# IMU_NoPilot.net
KiCad netlist of a schematic drawn in EAGLE
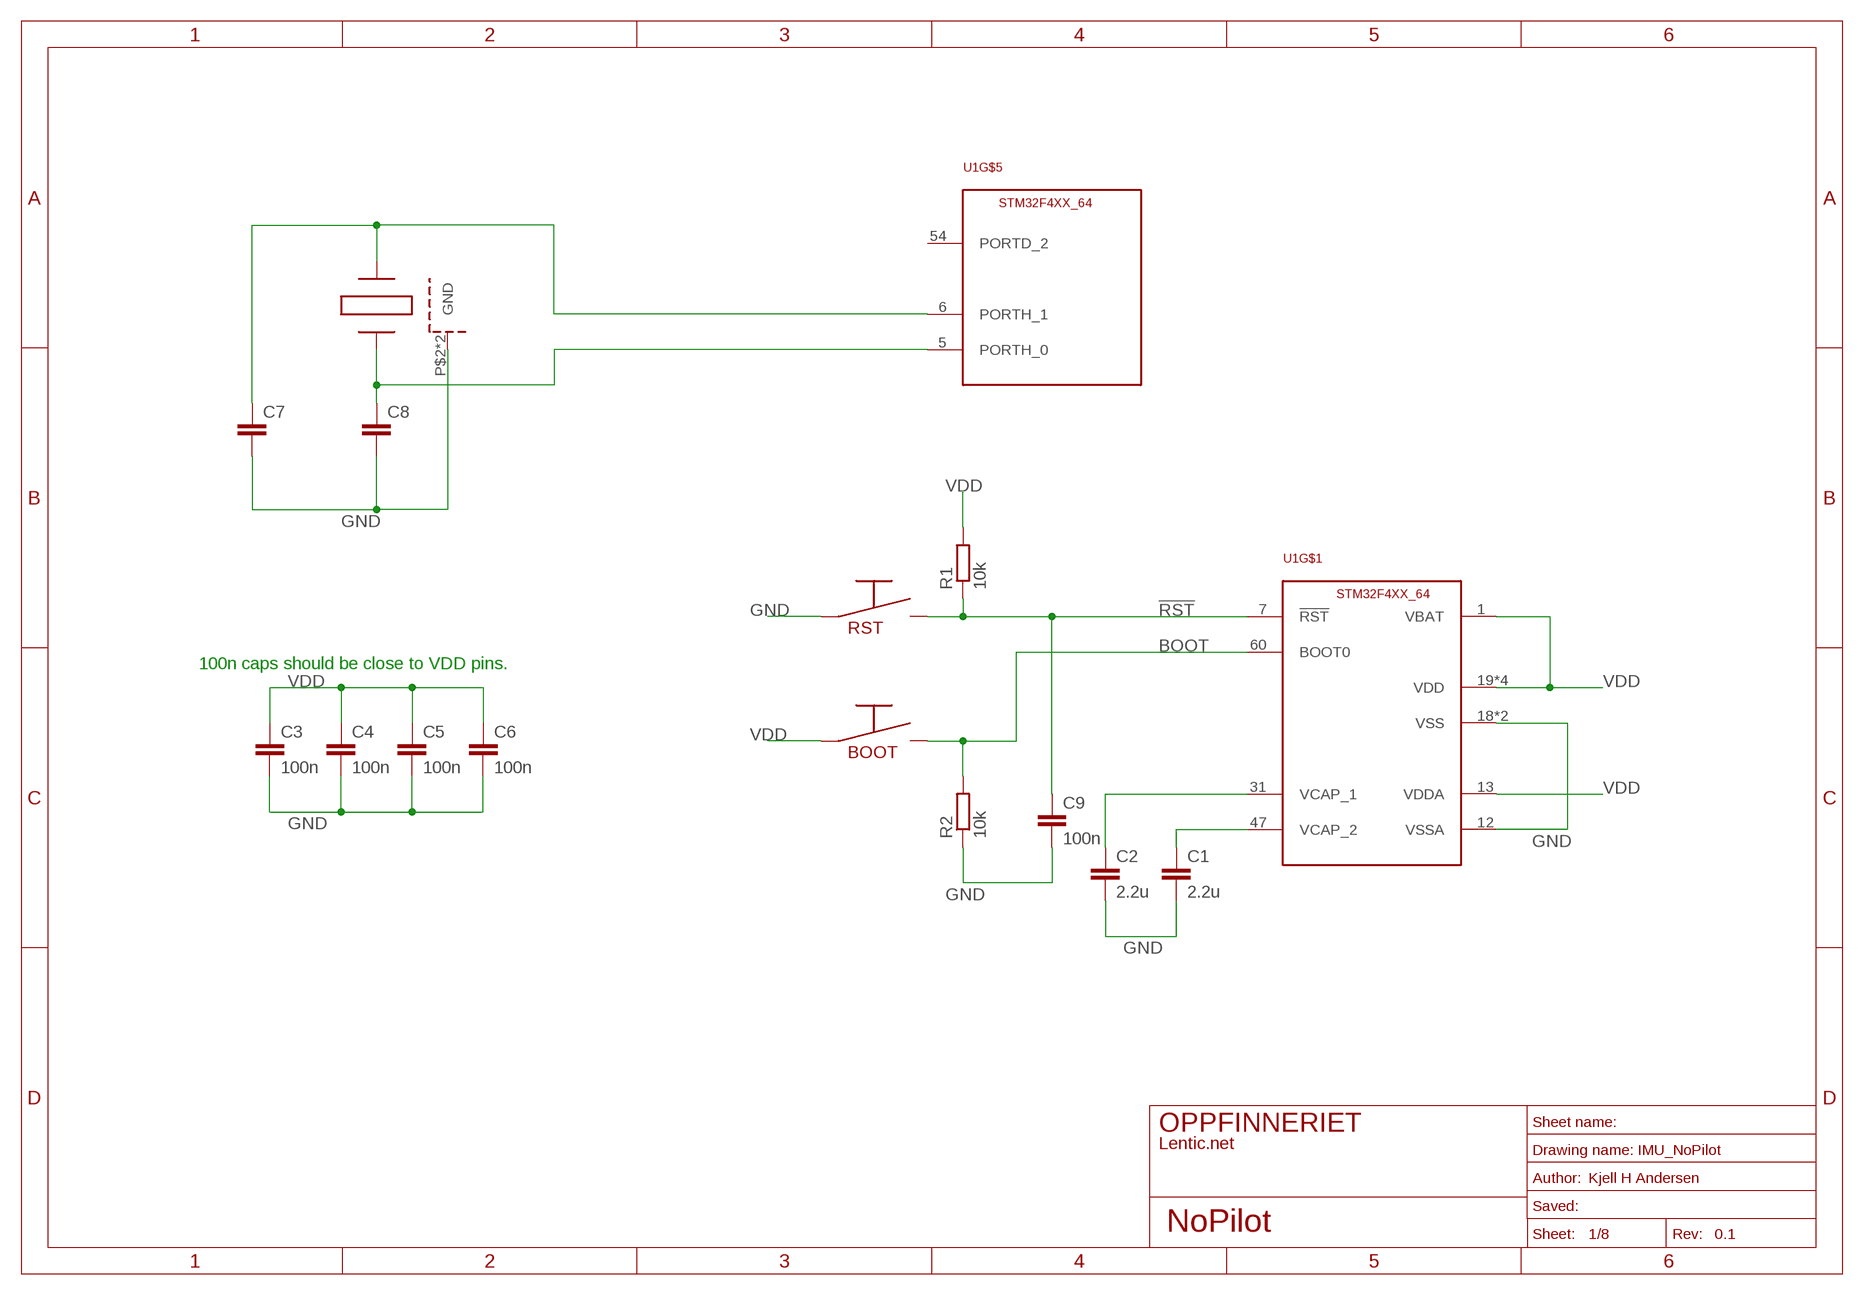
[diagram p0: schematic, sheet 1]
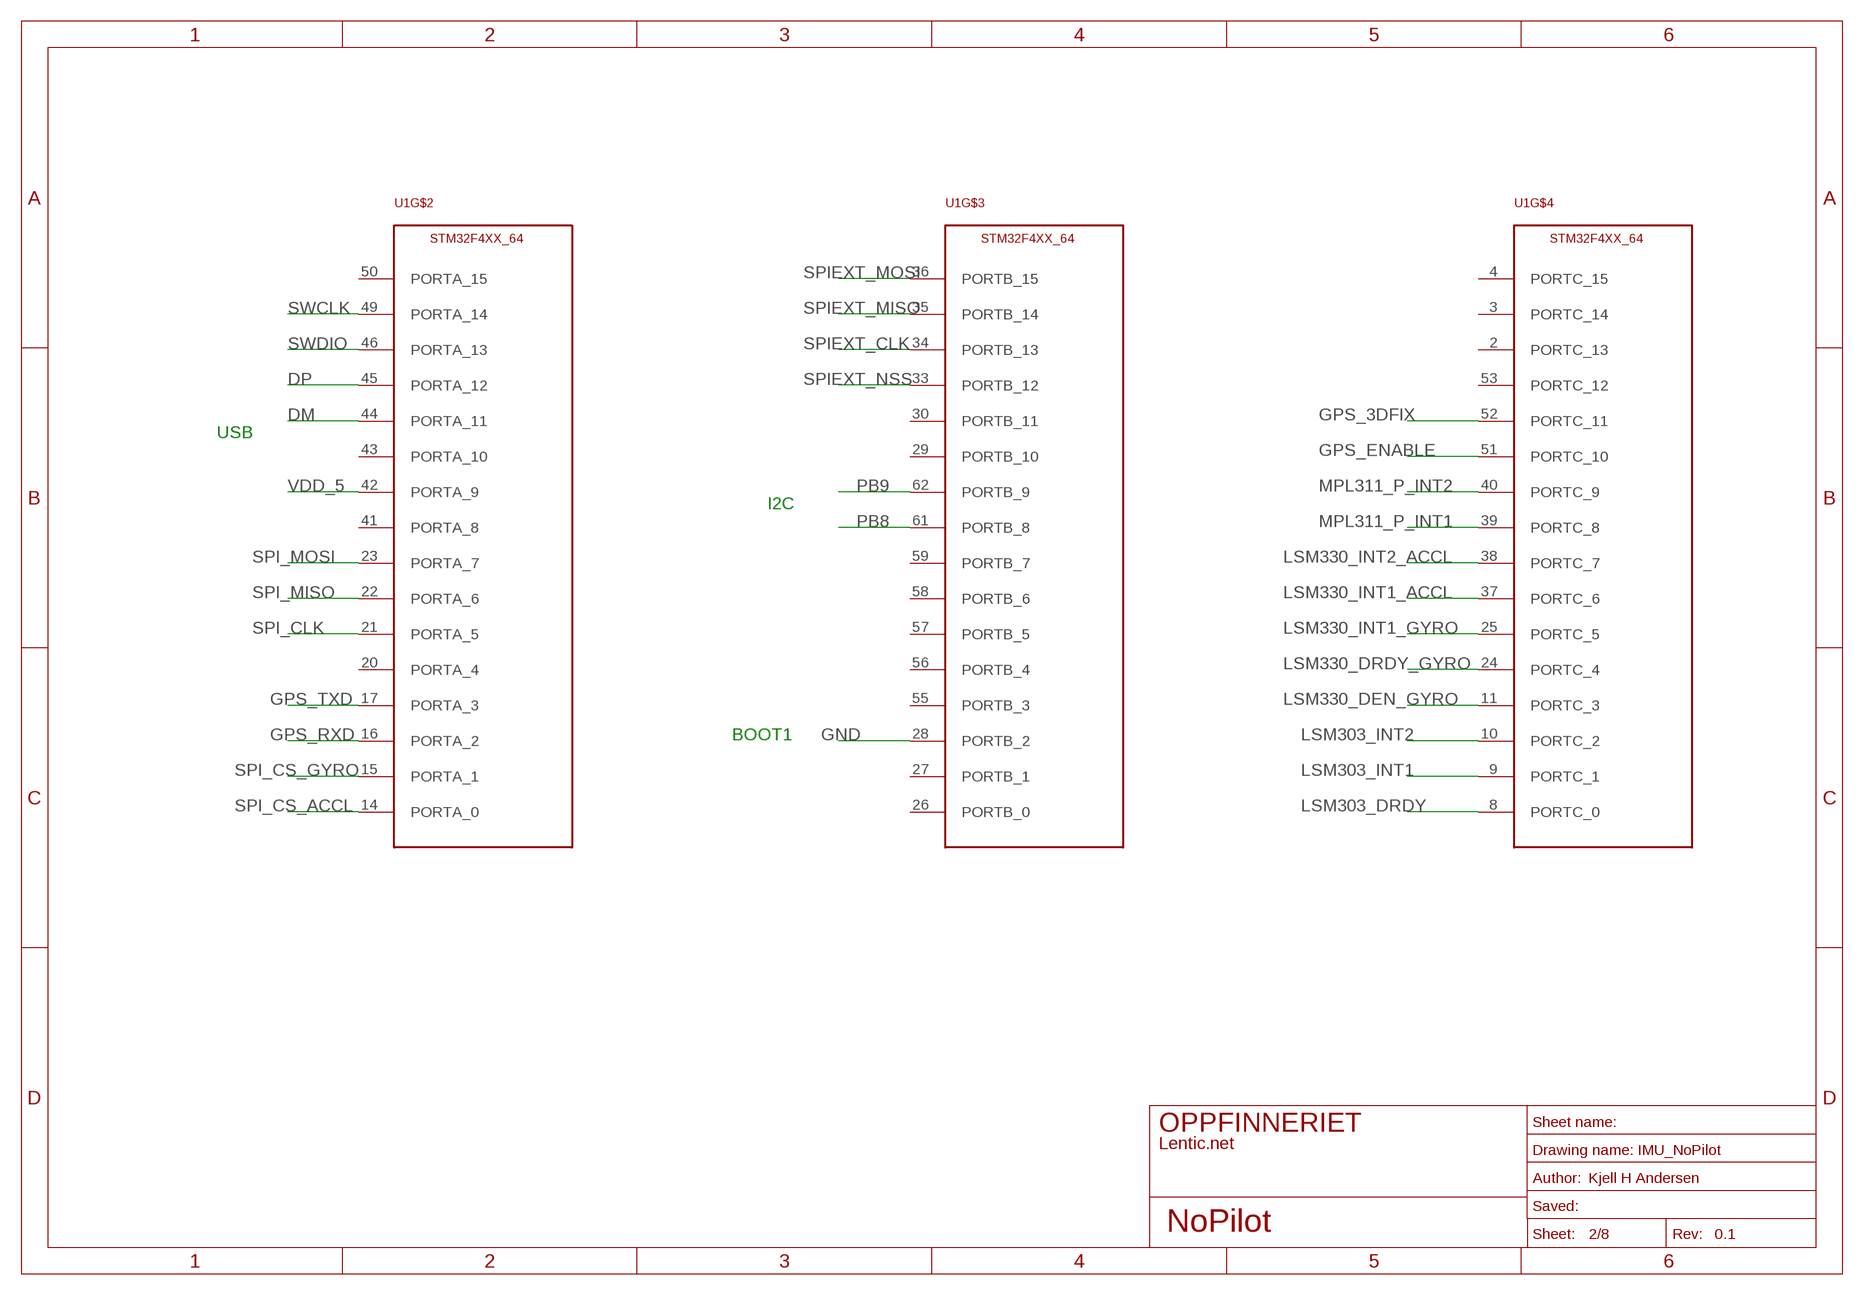
[diagram p1: schematic, sheet 2]
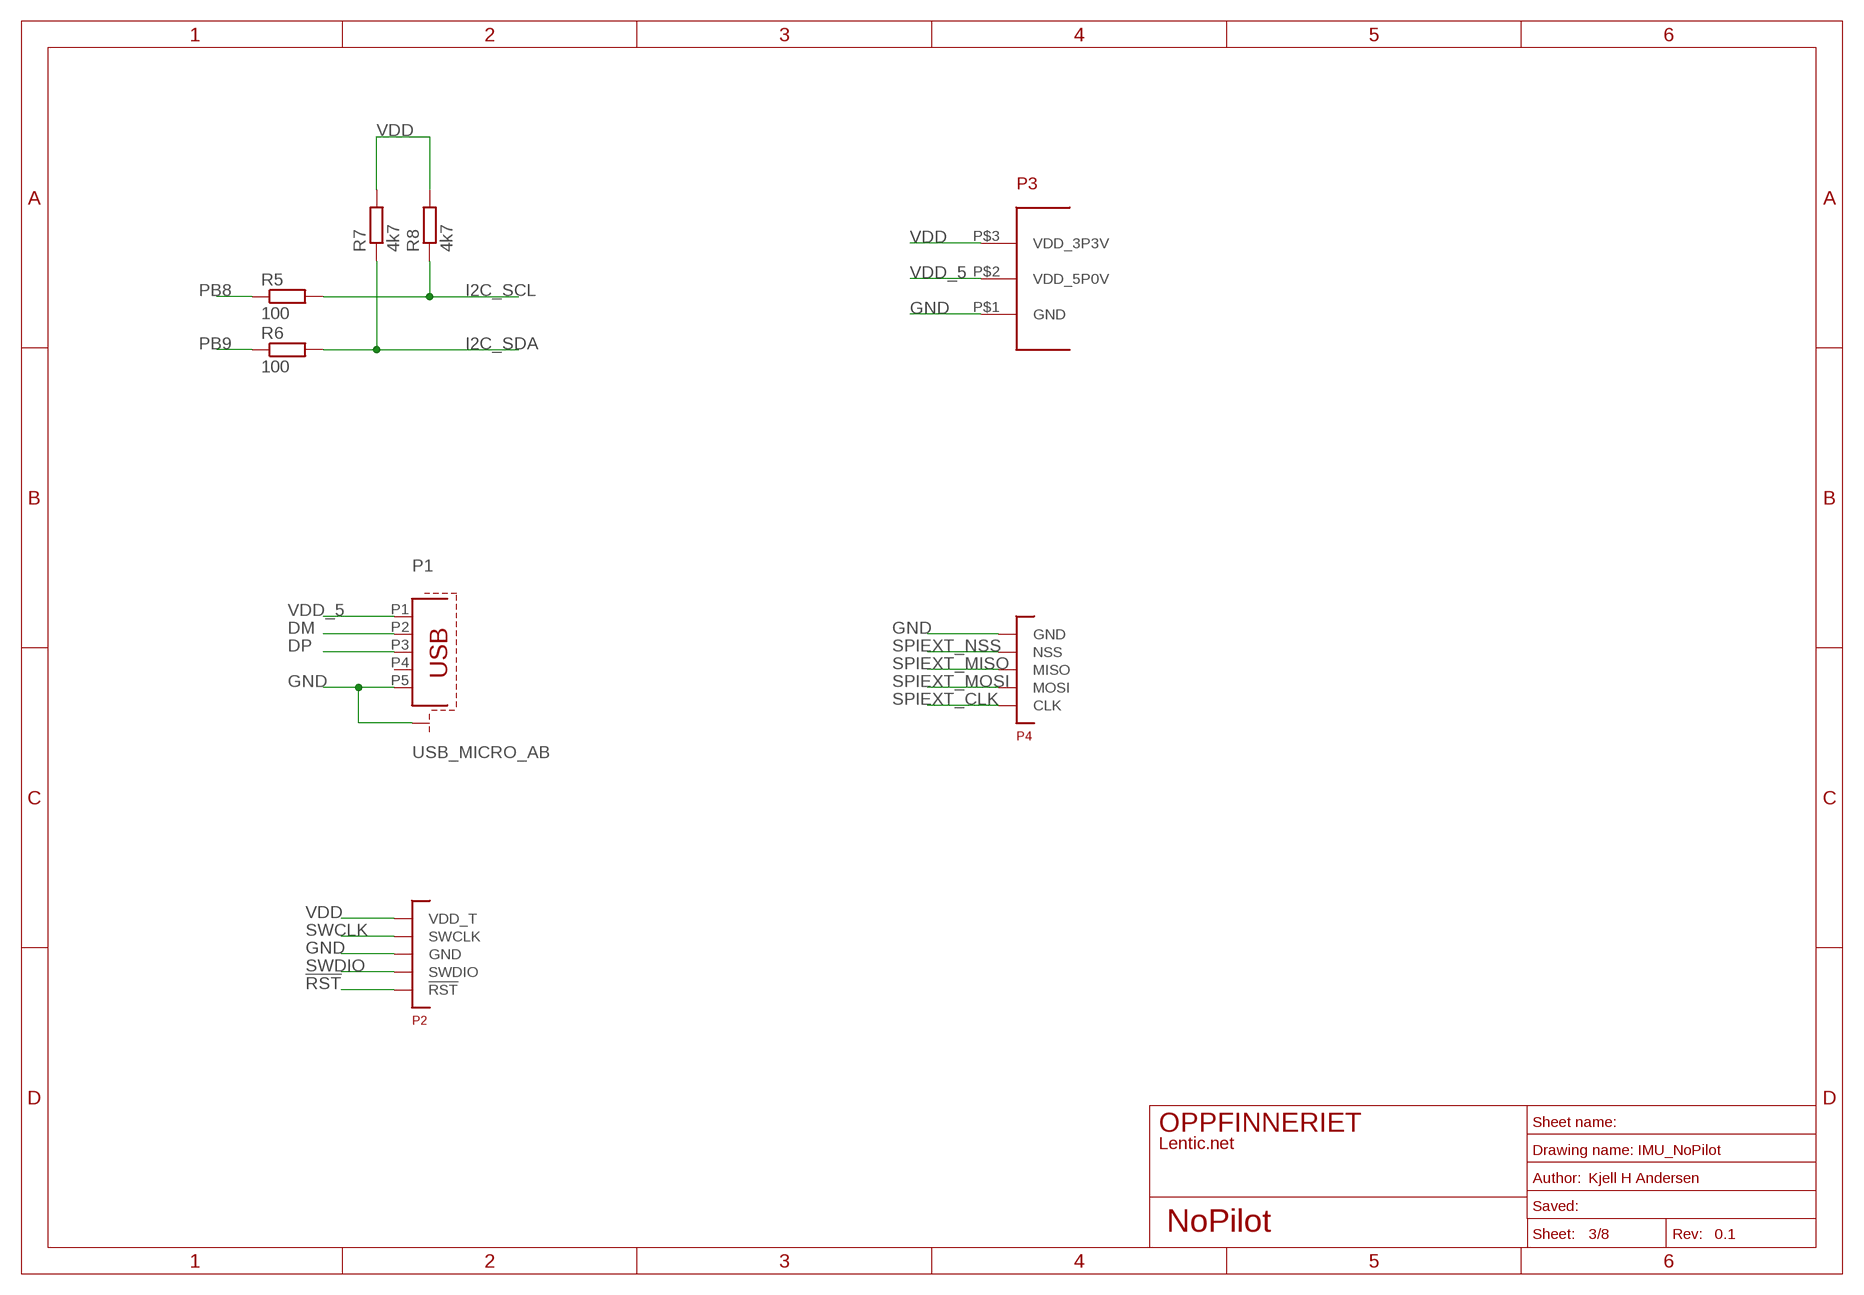
[diagram p2: schematic, sheet 3]
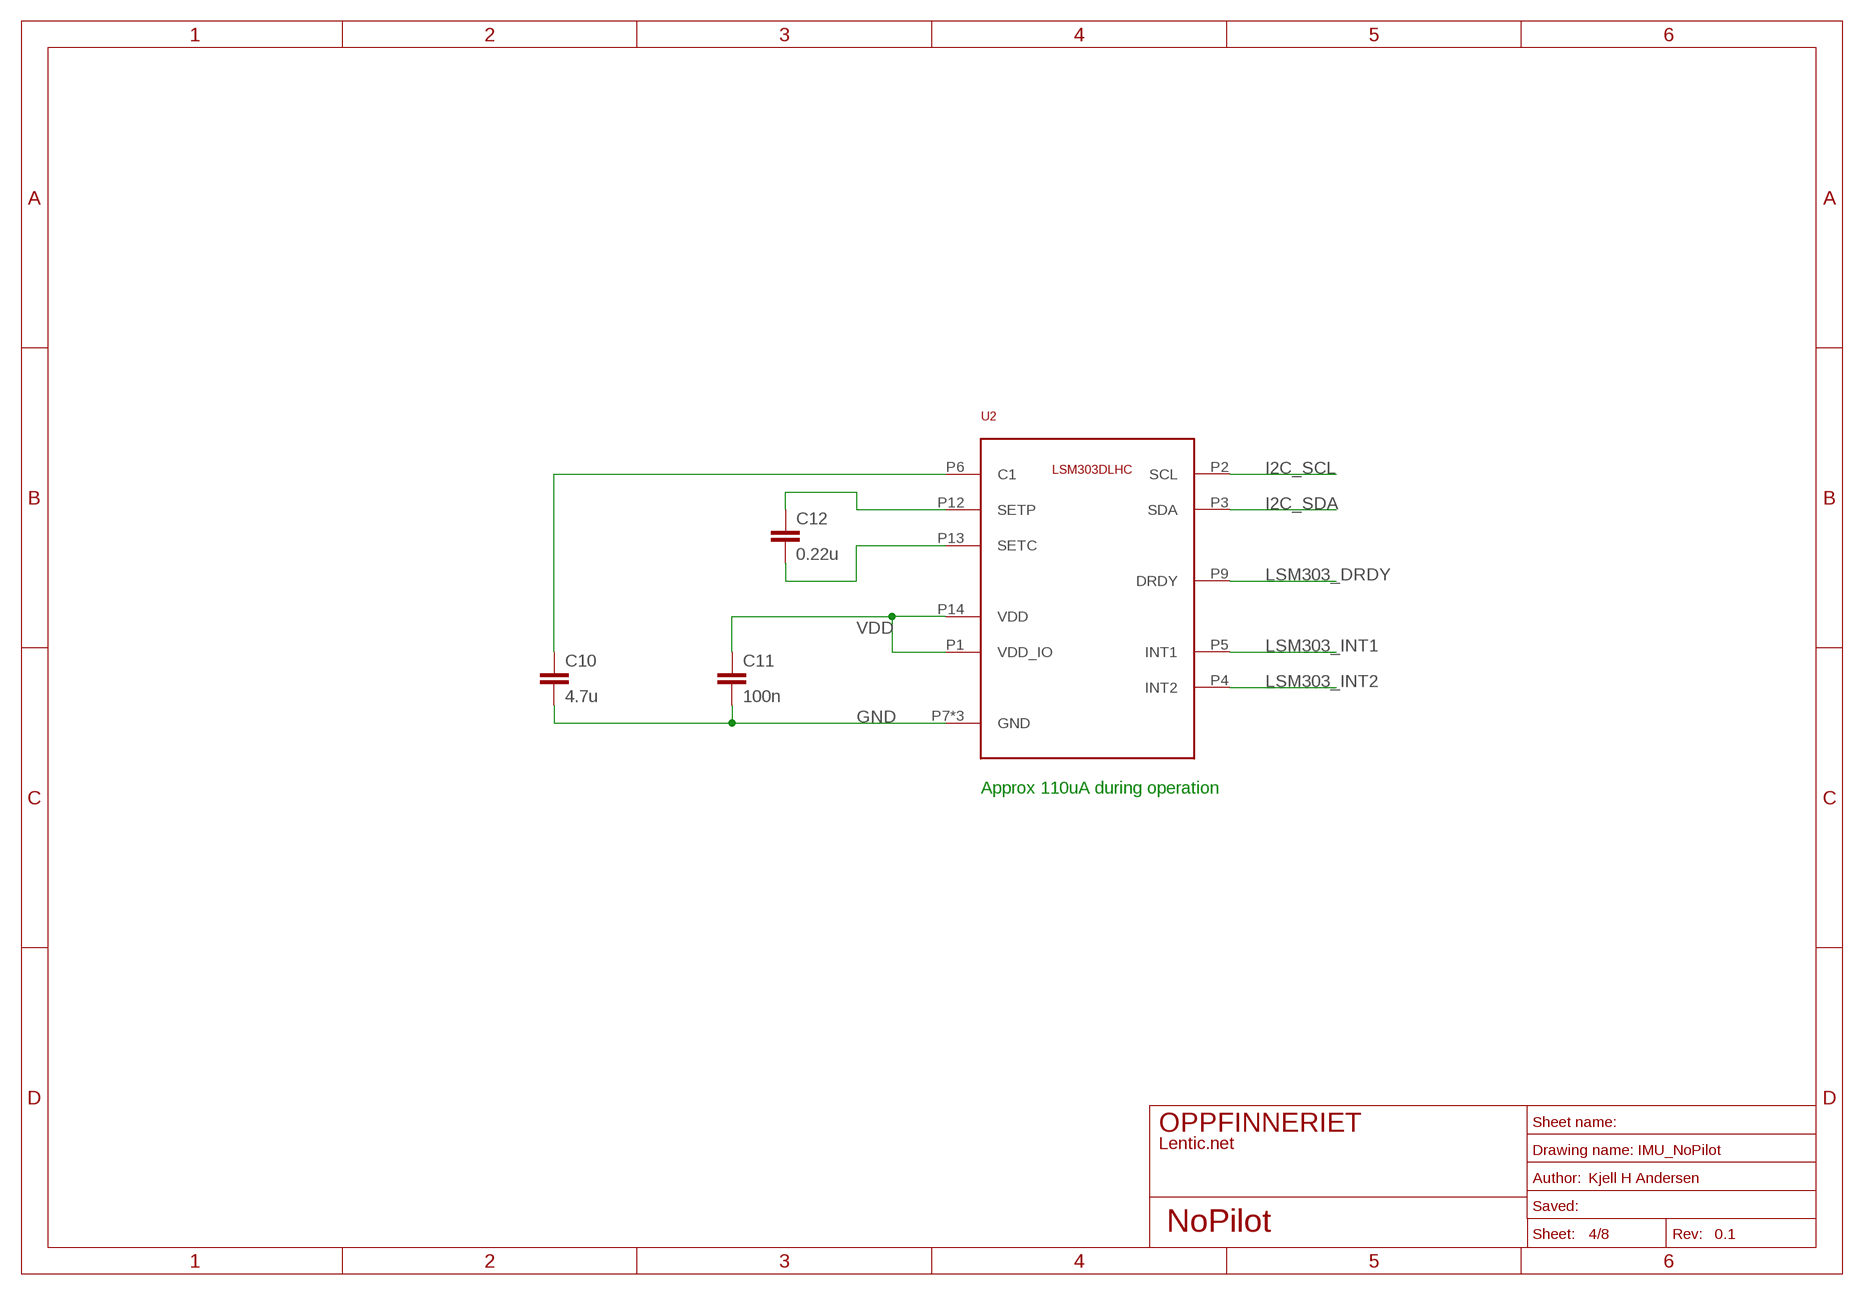
[diagram p3: schematic, sheet 4]
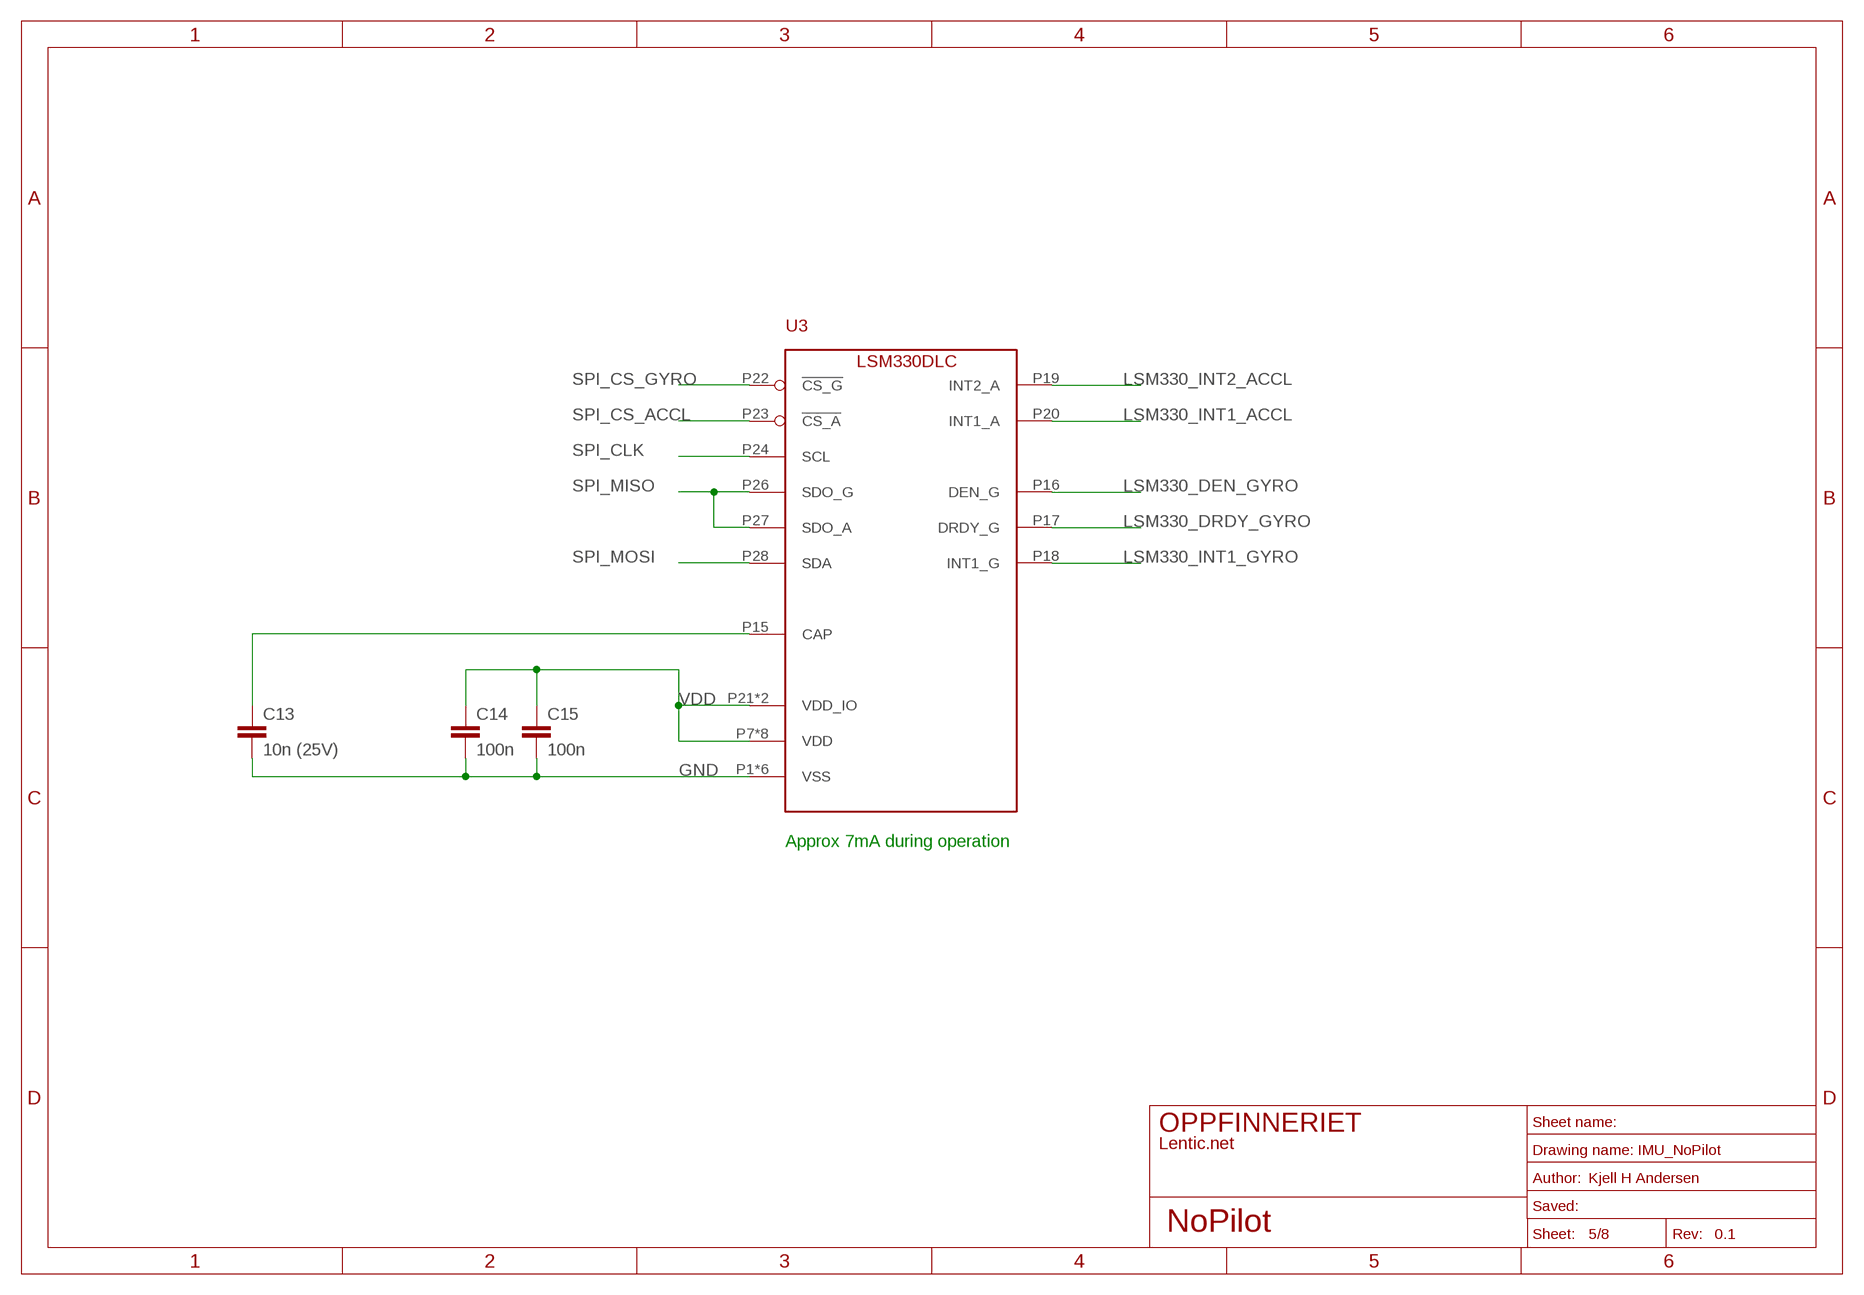
[diagram p4: schematic, sheet 5]
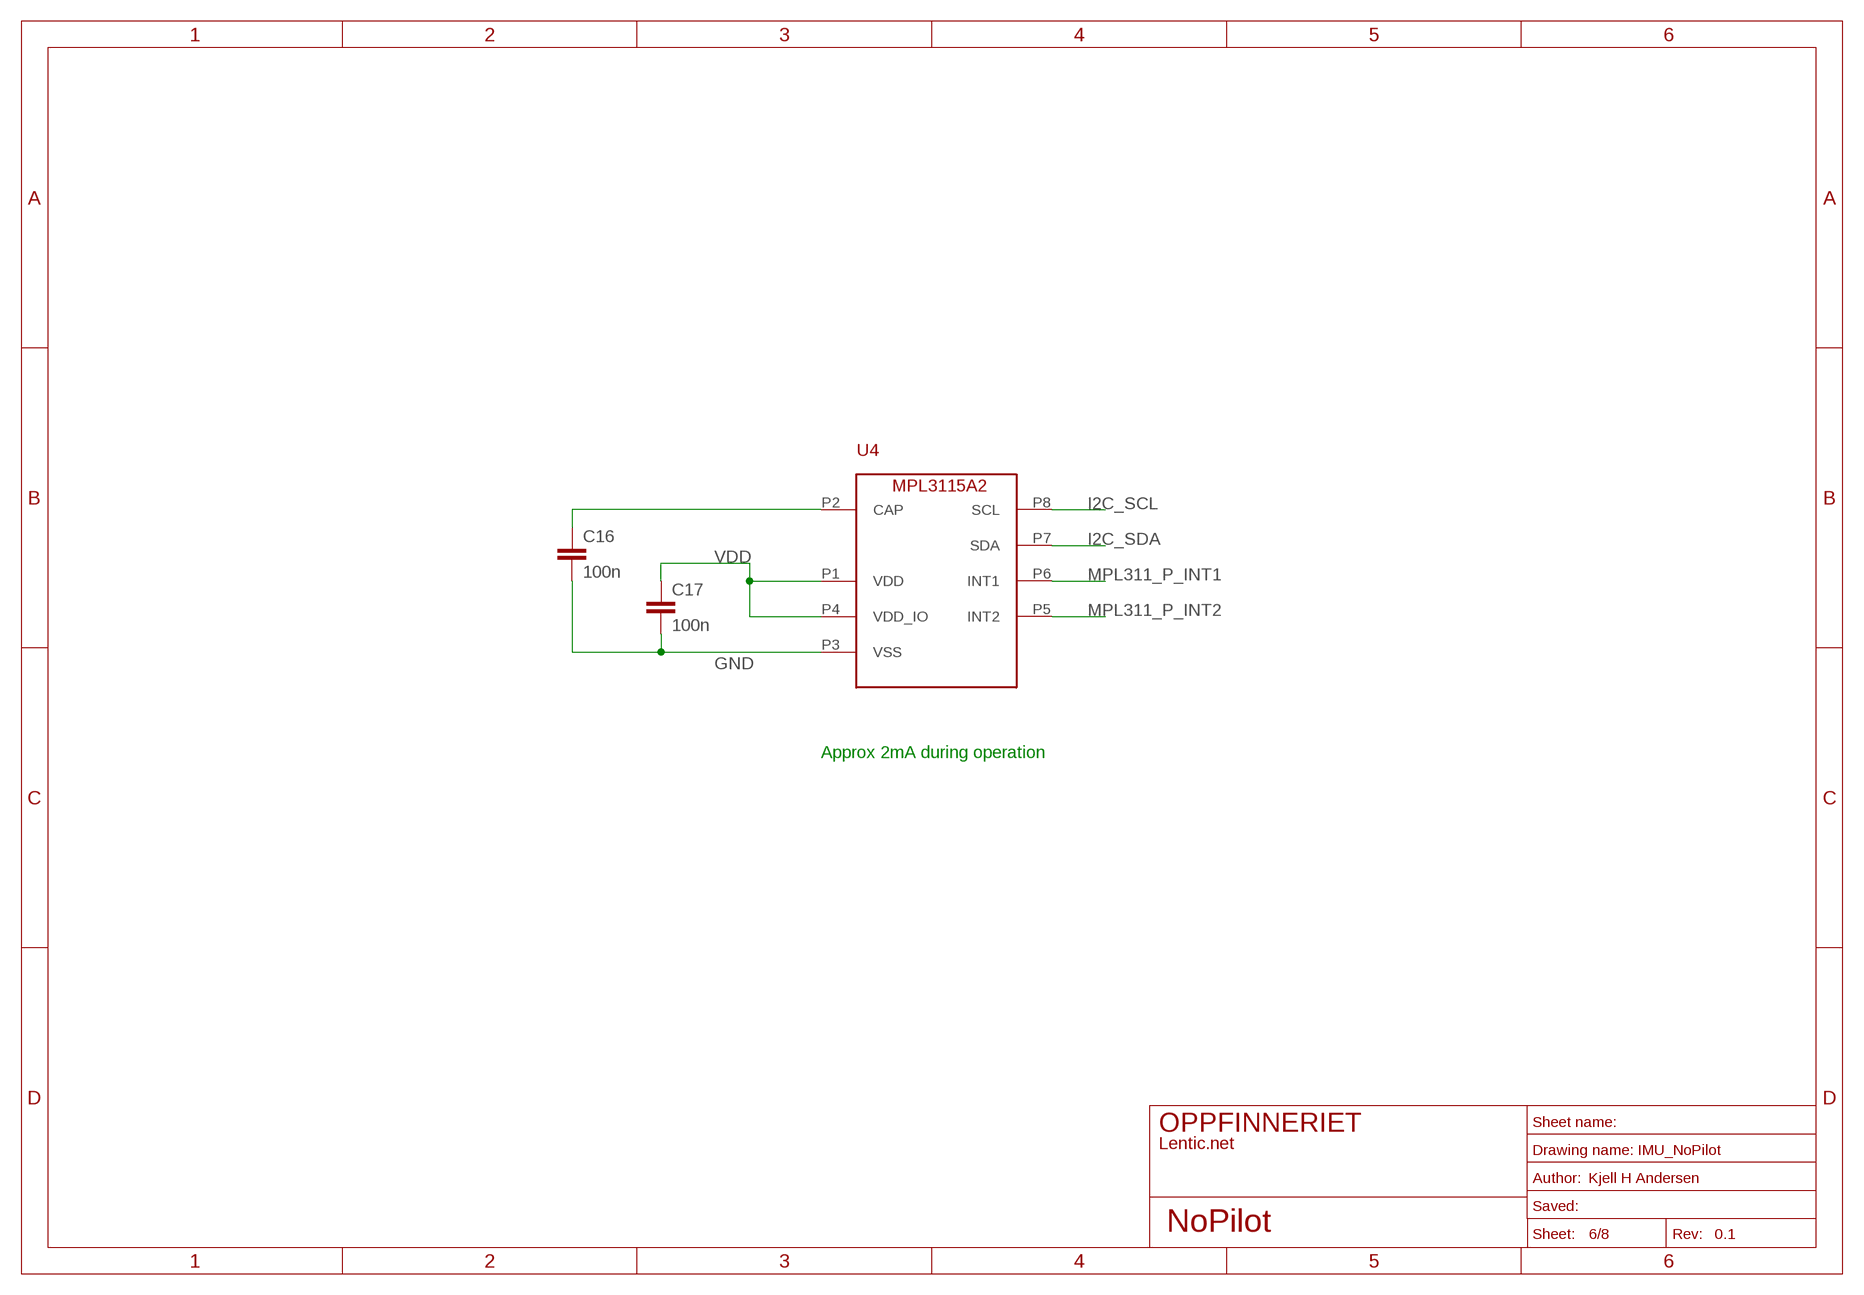
[diagram p5: schematic, sheet 6]
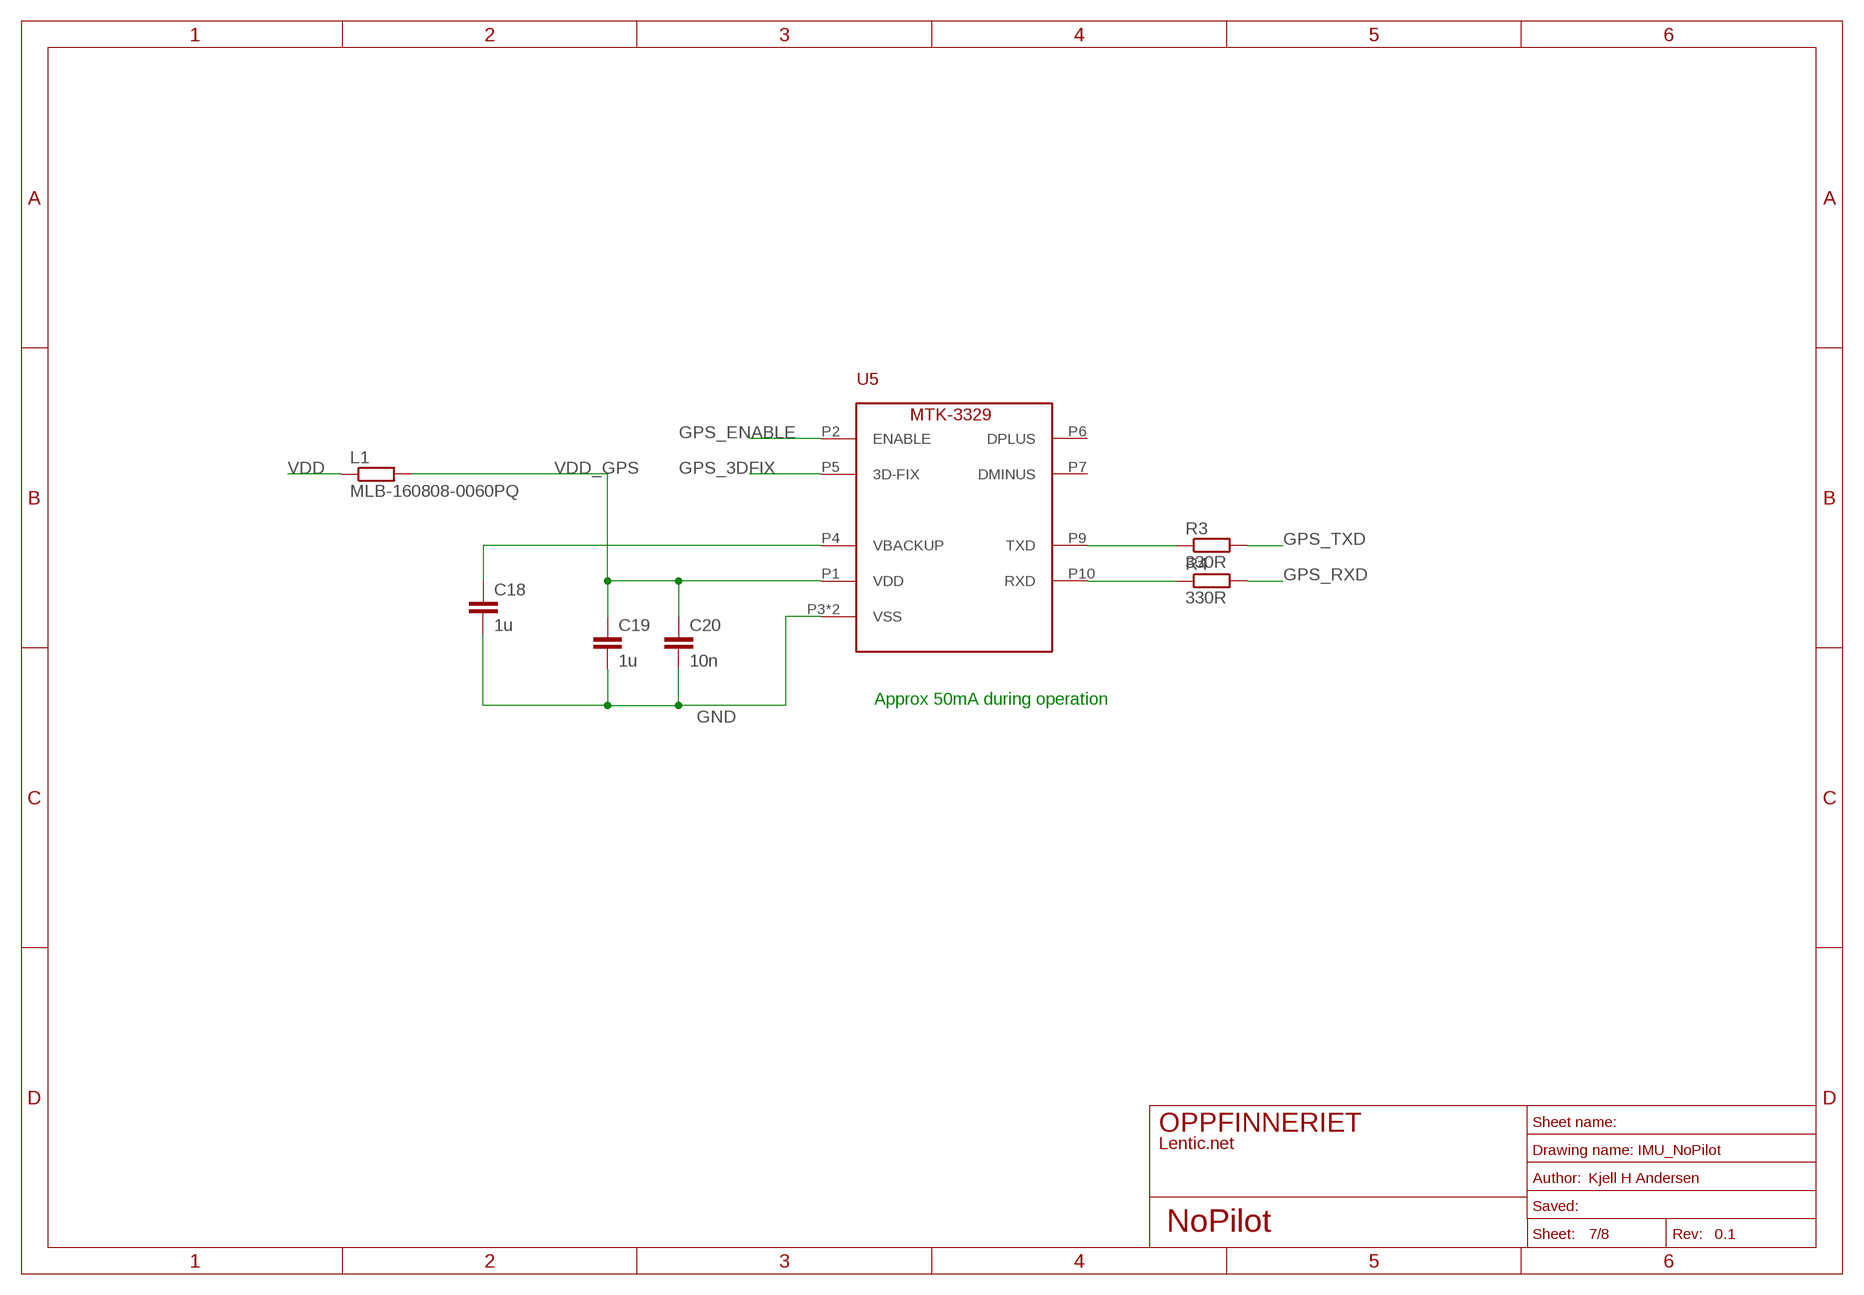
[diagram p6: schematic, sheet 7]
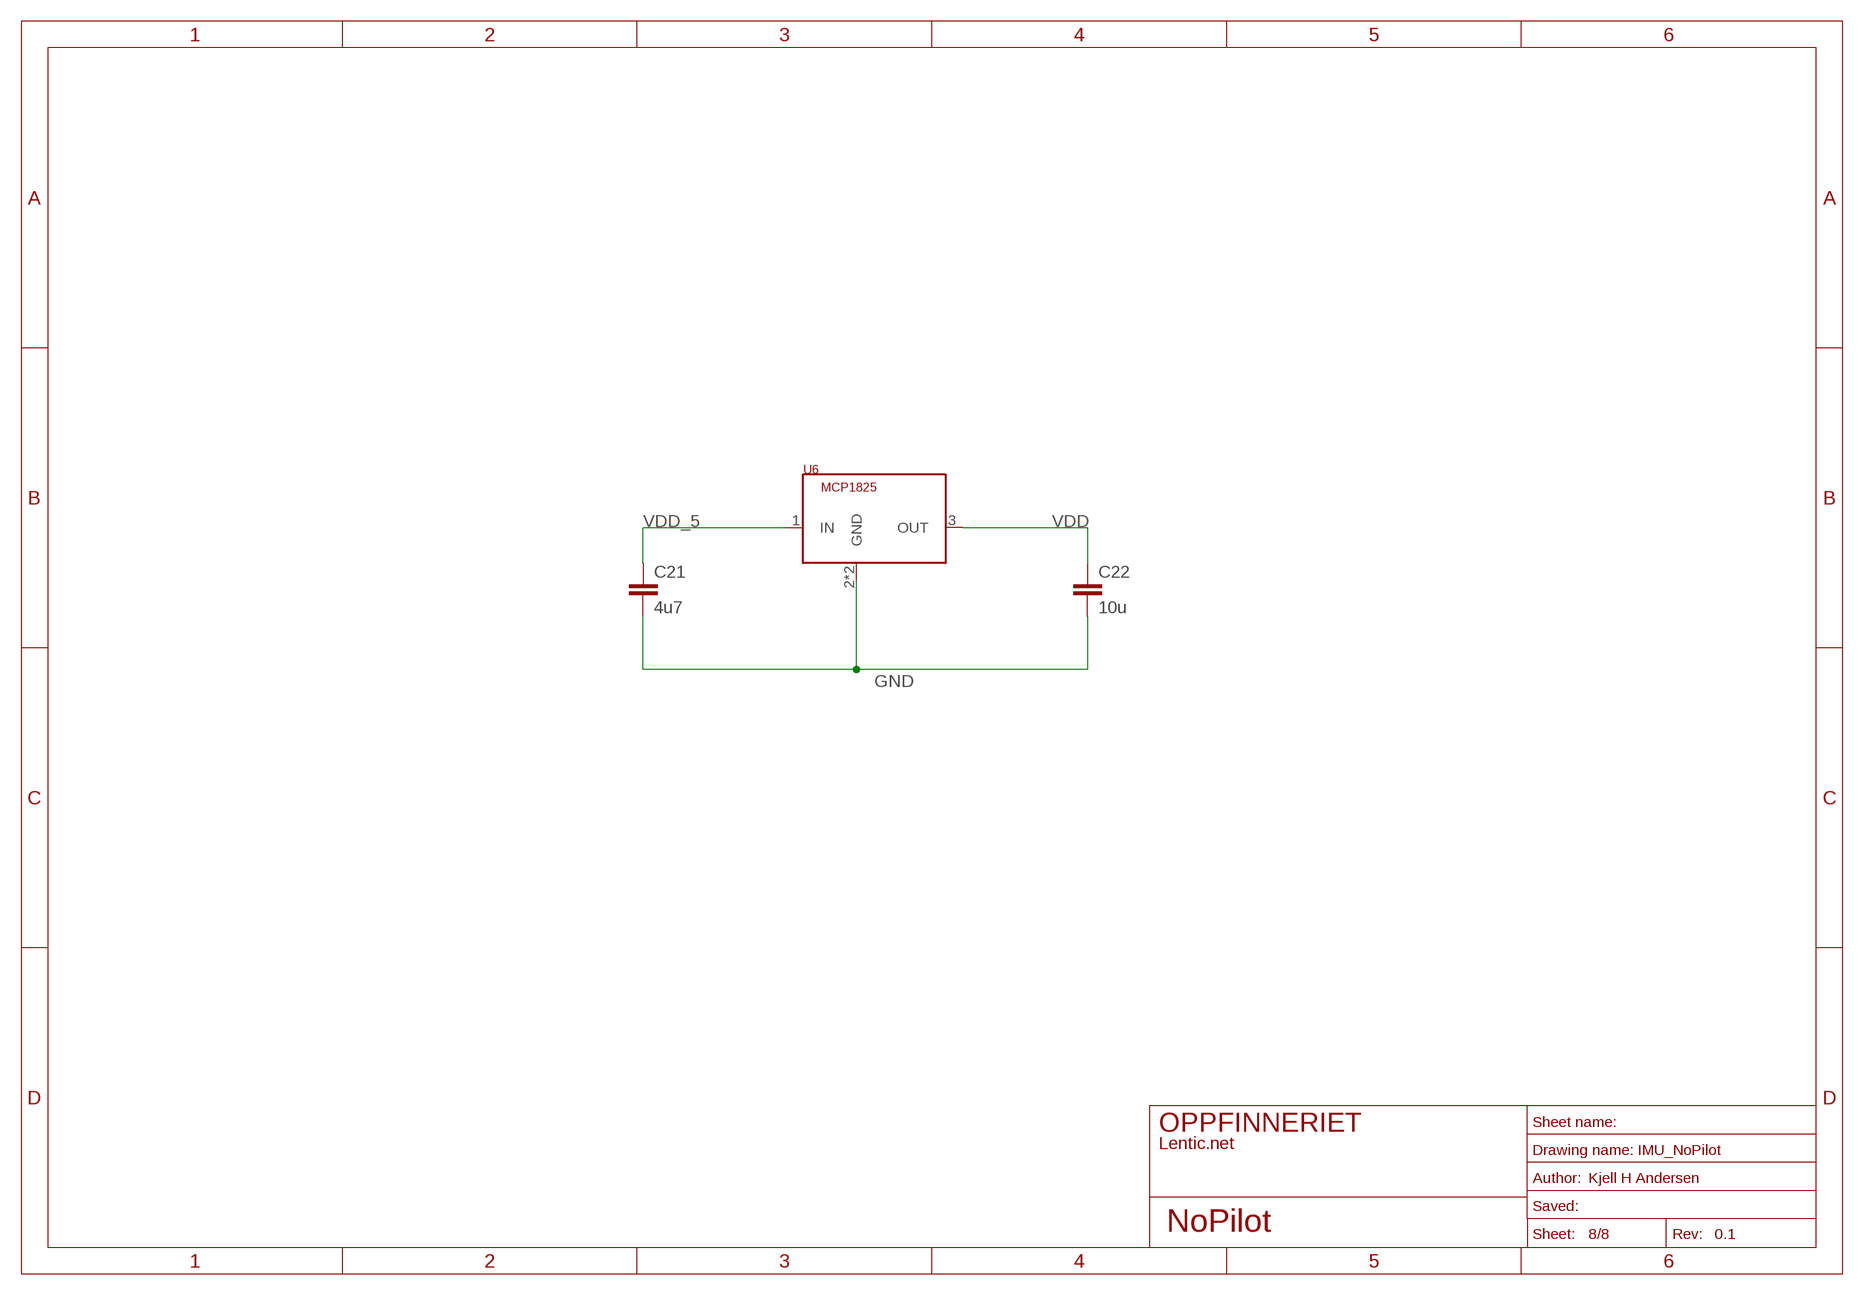
[diagram p7: schematic, sheet 8]

(export (version "E")
  (design (tool "Eeschema 10.0.6"))
  (components
    (comp (ref "C21")
      (value "4u7")
      (footprint "eagle-import:C0805")
      (libsource (lib "eagle-import") (part "C-EUC0805"))
    )
    (comp (ref "C22")
      (value "10u")
      (footprint "eagle-import:C0805")
      (libsource (lib "eagle-import") (part "C-EUC0805"))
    )
    (comp (ref "U6")
      (value "MCP1825")
      (footprint "eagle-import:SOT223")
      (libsource (lib "eagle-import") (part "MCP1825"))
    )
    (comp (ref "U1")
      (value "STM32F4XX_64")
      (footprint "eagle-import:TQFP64")
      (libsource (lib "eagle-import") (part "STM32F4XX_64"))
    )
    (comp (ref "P1")
      (value "USB_MICRO_AB")
      (footprint "eagle-import:USB_MICRO_AB")
      (libsource (lib "eagle-import") (part "USB_MICRO_AB"))
    )
    (comp (ref "P2")
      (value "ST_LINK")
      (footprint "eagle-import:ST_LINK")
      (libsource (lib "eagle-import") (part "ST_LINK"))
    )
    (comp (ref "P3")
      (value "PWR3")
      (footprint "eagle-import:PWR3")
      (libsource (lib "eagle-import") (part "PWR3"))
    )
    (comp (ref "P4")
      (value "SPI_EXT")
      (footprint "eagle-import:PINLIST5_2P54")
      (libsource (lib "eagle-import") (part "SPI_EXT"))
    )
    (comp (ref "R5")
      (value "100")
      (footprint "eagle-import:R0402")
      (libsource (lib "eagle-import") (part "R-EU_R0402"))
    )
    (comp (ref "R6")
      (value "100")
      (footprint "eagle-import:R0402")
      (libsource (lib "eagle-import") (part "R-EU_R0402"))
    )
    (comp (ref "R7")
      (value "4k7")
      (footprint "eagle-import:R0402")
      (libsource (lib "eagle-import") (part "R-EU_R0402"))
    )
    (comp (ref "R8")
      (value "4k7")
      (footprint "eagle-import:R0402")
      (libsource (lib "eagle-import") (part "R-EU_R0402"))
    )
    (comp (ref "BOOT")
      (value "OMRON_B3FS_1000")
      (footprint "eagle-import:OMROM_B3FS-1XXX")
      (libsource (lib "eagle-import") (part "OMRON_B3FS_1000"))
    )
    (comp (ref "C1")
      (value "2.2u")
      (footprint "eagle-import:C0805")
      (libsource (lib "eagle-import") (part "C-EUC0805"))
    )
    (comp (ref "C2")
      (value "2.2u")
      (footprint "eagle-import:C0805")
      (libsource (lib "eagle-import") (part "C-EUC0805"))
    )
    (comp (ref "C3")
      (value "100n")
      (footprint "eagle-import:C0402")
      (libsource (lib "eagle-import") (part "C-EUC0402"))
    )
    (comp (ref "C4")
      (value "100n")
      (footprint "eagle-import:C0402")
      (libsource (lib "eagle-import") (part "C-EUC0402"))
    )
    (comp (ref "C5")
      (value "100n")
      (footprint "eagle-import:C0402")
      (libsource (lib "eagle-import") (part "C-EUC0402"))
    )
    (comp (ref "C6")
      (value "100n")
      (footprint "eagle-import:C0402")
      (libsource (lib "eagle-import") (part "C-EUC0402"))
    )
    (comp (ref "C7")
      (value "C-EUC0402")
      (footprint "eagle-import:C0402")
      (libsource (lib "eagle-import") (part "C-EUC0402"))
    )
    (comp (ref "C8")
      (value "C-EUC0402")
      (footprint "eagle-import:C0402")
      (libsource (lib "eagle-import") (part "C-EUC0402"))
    )
    (comp (ref "C9")
      (value "100n")
      (footprint "eagle-import:C0402")
      (libsource (lib "eagle-import") (part "C-EUC0402"))
    )
    (comp (ref "R1")
      (value "10k")
      (footprint "eagle-import:R0402")
      (libsource (lib "eagle-import") (part "R-EU_R0402"))
    )
    (comp (ref "R2")
      (value "10k")
      (footprint "eagle-import:R0402")
      (libsource (lib "eagle-import") (part "R-EU_R0402"))
    )
    (comp (ref "RST")
      (value "OMRON_B3FS_1000")
      (footprint "eagle-import:OMROM_B3FS-1XXX")
      (libsource (lib "eagle-import") (part "OMRON_B3FS_1000"))
    )
    (comp (ref "XTAL1")
      (value "XTAL_5X3P2")
      (footprint "eagle-import:XTAL_5X3P2")
      (libsource (lib "eagle-import") (part "XTAL_5X3P2"))
    )
    (comp (ref "C18")
      (value "1u")
      (footprint "eagle-import:C0805")
      (libsource (lib "eagle-import") (part "C-EUC0805"))
    )
    (comp (ref "C19")
      (value "1u")
      (footprint "eagle-import:C0805")
      (libsource (lib "eagle-import") (part "C-EUC0805"))
    )
    (comp (ref "C20")
      (value "10n")
      (footprint "eagle-import:C0402")
      (libsource (lib "eagle-import") (part "C-EUC0402"))
    )
    (comp (ref "L1")
      (value "MLB-160808-0060PQ")
      (footprint "eagle-import:R0603")
      (libsource (lib "eagle-import") (part "R-EU_R0603"))
    )
    (comp (ref "R3")
      (value "330R")
      (footprint "eagle-import:R0402")
      (libsource (lib "eagle-import") (part "R-EU_R0402"))
    )
    (comp (ref "R4")
      (value "330R")
      (footprint "eagle-import:R0402")
      (libsource (lib "eagle-import") (part "R-EU_R0402"))
    )
    (comp (ref "U5")
      (value "MTK-3329")
      (footprint "eagle-import:MTK-3329")
      (libsource (lib "eagle-import") (part "MTK-3329"))
    )
    (comp (ref "C16")
      (value "100n")
      (footprint "eagle-import:C0402")
      (libsource (lib "eagle-import") (part "C-EUC0402"))
    )
    (comp (ref "C17")
      (value "100n")
      (footprint "eagle-import:C0402")
      (libsource (lib "eagle-import") (part "C-EUC0402"))
    )
    (comp (ref "U4")
      (value "MPL3115A2")
      (footprint "eagle-import:LGA_3X5_8")
      (libsource (lib "eagle-import") (part "MPL3115A2"))
    )
    (comp (ref "C10")
      (value "4.7u")
      (footprint "eagle-import:C0805")
      (libsource (lib "eagle-import") (part "C-EUC0805"))
    )
    (comp (ref "C11")
      (value "100n")
      (footprint "eagle-import:C0402")
      (libsource (lib "eagle-import") (part "C-EUC0402"))
    )
    (comp (ref "C12")
      (value "0.22u")
      (footprint "eagle-import:C0402")
      (libsource (lib "eagle-import") (part "C-EUC0402"))
    )
    (comp (ref "U2")
      (value "LSM303DLHC")
      (footprint "eagle-import:LGA_3X5X1_14L")
      (libsource (lib "eagle-import") (part "LSM303DLHC"))
    )
    (comp (ref "C13")
      (value "10n (25V)")
      (footprint "eagle-import:C0402")
      (libsource (lib "eagle-import") (part "C-EUC0402"))
    )
    (comp (ref "C14")
      (value "100n")
      (footprint "eagle-import:C0402")
      (libsource (lib "eagle-import") (part "C-EUC0402"))
    )
    (comp (ref "C15")
      (value "100n")
      (footprint "eagle-import:C0402")
      (libsource (lib "eagle-import") (part "C-EUC0402"))
    )
    (comp (ref "U3")
      (value "LSM330DLC")
      (footprint "eagle-import:LGA_4X5X1P1_28L")
      (libsource (lib "eagle-import") (part "LSM330DLC"))
    )
  )
  (nets
    (net (code "1") (name "BOOT") (class "Default")
      (node (ref "BOOT") (pin "P3") (pinfunction "P$2_P3") (pintype "bidirectional"))
      (node (ref "BOOT") (pin "P4") (pinfunction "P$2_P4") (pintype "bidirectional"))
      (node (ref "R2") (pin "2") (pinfunction "2_2") (pintype "passive"))
      (node (ref "U1") (pin "60") (pinfunction "BOOT0_60") (pintype "bidirectional"))
    )
    (net (code "2") (name "DM") (class "Default")
      (node (ref "P1") (pin "P2") (pinfunction "2_P2") (pintype "passive"))
      (node (ref "U1") (pin "44") (pinfunction "PORTA_11_44") (pintype "bidirectional"))
    )
    (net (code "3") (name "DP") (class "Default")
      (node (ref "P1") (pin "P3") (pinfunction "3_P3") (pintype "passive"))
      (node (ref "U1") (pin "45") (pinfunction "PORTA_12_45") (pintype "bidirectional"))
    )
    (net (code "4") (name "GND") (class "Default")
      (node (ref "C1") (pin "2") (pinfunction "2_2") (pintype "passive"))
      (node (ref "C10") (pin "2") (pinfunction "2_2") (pintype "passive"))
      (node (ref "C11") (pin "2") (pinfunction "2_2") (pintype "passive"))
      (node (ref "C13") (pin "2") (pinfunction "2_2") (pintype "passive"))
      (node (ref "C14") (pin "2") (pinfunction "2_2") (pintype "passive"))
      (node (ref "C15") (pin "2") (pinfunction "2_2") (pintype "passive"))
      (node (ref "C16") (pin "2") (pinfunction "2_2") (pintype "passive"))
      (node (ref "C17") (pin "2") (pinfunction "2_2") (pintype "passive"))
      (node (ref "C18") (pin "2") (pinfunction "2_2") (pintype "passive"))
      (node (ref "C19") (pin "2") (pinfunction "2_2") (pintype "passive"))
      (node (ref "C2") (pin "2") (pinfunction "2_2") (pintype "passive"))
      (node (ref "C20") (pin "2") (pinfunction "2_2") (pintype "passive"))
      (node (ref "C21") (pin "2") (pinfunction "2_2") (pintype "passive"))
      (node (ref "C22") (pin "2") (pinfunction "2_2") (pintype "passive"))
      (node (ref "C3") (pin "2") (pinfunction "2_2") (pintype "passive"))
      (node (ref "C4") (pin "2") (pinfunction "2_2") (pintype "passive"))
      (node (ref "C5") (pin "2") (pinfunction "2_2") (pintype "passive"))
      (node (ref "C6") (pin "2") (pinfunction "2_2") (pintype "passive"))
      (node (ref "C7") (pin "2") (pinfunction "2_2") (pintype "passive"))
      (node (ref "C8") (pin "2") (pinfunction "2_2") (pintype "passive"))
      (node (ref "C9") (pin "2") (pinfunction "2_2") (pintype "passive"))
      (node (ref "P1") (pin "NC1") (pinfunction "S1_NC1") (pintype "passive"))
      (node (ref "P1") (pin "NC2") (pinfunction "S1_NC2") (pintype "passive"))
      (node (ref "P1") (pin "NC3") (pinfunction "S1_NC3") (pintype "passive"))
      (node (ref "P1") (pin "NC4") (pinfunction "S1_NC4") (pintype "passive"))
      (node (ref "P1") (pin "NC5") (pinfunction "S1_NC5") (pintype "passive"))
      (node (ref "P1") (pin "NC6") (pinfunction "S1_NC6") (pintype "passive"))
      (node (ref "P1") (pin "P5") (pinfunction "5_P5") (pintype "passive"))
      (node (ref "P2") (pin "P$3") (pinfunction "GND_P$3") (pintype "bidirectional"))
      (node (ref "P3") (pin "P$1") (pinfunction "GND_P$1") (pintype "bidirectional"))
      (node (ref "P4") (pin "P$5") (pinfunction "GND_P$5") (pintype "bidirectional"))
      (node (ref "R2") (pin "1") (pinfunction "1_1") (pintype "passive"))
      (node (ref "RST") (pin "P1") (pinfunction "P$1_P1") (pintype "bidirectional"))
      (node (ref "RST") (pin "P2") (pinfunction "P$1_P2") (pintype "bidirectional"))
      (node (ref "U1") (pin "12") (pinfunction "VSSA_12") (pintype "bidirectional"))
      (node (ref "U1") (pin "18") (pinfunction "VSS_18") (pintype "bidirectional"))
      (node (ref "U1") (pin "28") (pinfunction "PORTB_2_28") (pintype "bidirectional"))
      (node (ref "U1") (pin "63") (pinfunction "VSS_63") (pintype "bidirectional"))
      (node (ref "U2") (pin "P10") (pinfunction "GND_P10") (pintype "bidirectional"))
      (node (ref "U2") (pin "P11") (pinfunction "GND_P11") (pintype "bidirectional"))
      (node (ref "U2") (pin "P7") (pinfunction "GND_P7") (pintype "bidirectional"))
      (node (ref "U3") (pin "P1") (pinfunction "VSS_P1") (pintype "power_in"))
      (node (ref "U3") (pin "P2") (pinfunction "VSS_P2") (pintype "power_in"))
      (node (ref "U3") (pin "P3") (pinfunction "VSS_P3") (pintype "power_in"))
      (node (ref "U3") (pin "P4") (pinfunction "VSS_P4") (pintype "power_in"))
      (node (ref "U3") (pin "P5") (pinfunction "VSS_P5") (pintype "power_in"))
      (node (ref "U3") (pin "P6") (pinfunction "VSS_P6") (pintype "power_in"))
      (node (ref "U4") (pin "P3") (pinfunction "VSS_P3") (pintype "power_in"))
      (node (ref "U5") (pin "P3") (pinfunction "VSS_P3") (pintype "bidirectional"))
      (node (ref "U5") (pin "P8") (pinfunction "VSS_P8") (pintype "bidirectional"))
      (node (ref "U6") (pin "2") (pinfunction "GND_2") (pintype "bidirectional"))
      (node (ref "U6") (pin "4") (pinfunction "GND_4") (pintype "bidirectional"))
      (node (ref "XTAL1") (pin "P$2") (pinfunction "GND_P$2") (pintype "bidirectional"))
      (node (ref "XTAL1") (pin "P$4") (pinfunction "GND_P$4") (pintype "bidirectional"))
    )
    (net (code "5") (name "GPS_3DFIX") (class "Default")
      (node (ref "U1") (pin "52") (pinfunction "PORTC_11_52") (pintype "bidirectional"))
      (node (ref "U5") (pin "P5") (pinfunction "3D-FIX_P5") (pintype "bidirectional"))
    )
    (net (code "6") (name "GPS_ENABLE") (class "Default")
      (node (ref "U1") (pin "51") (pinfunction "PORTC_10_51") (pintype "bidirectional"))
      (node (ref "U5") (pin "P2") (pinfunction "ENABLE_P2") (pintype "bidirectional"))
    )
    (net (code "7") (name "GPS_RXD") (class "Default")
      (node (ref "R4") (pin "2") (pinfunction "2_2") (pintype "passive"))
      (node (ref "U1") (pin "16") (pinfunction "PORTA_2_16") (pintype "bidirectional"))
    )
    (net (code "8") (name "GPS_TXD") (class "Default")
      (node (ref "R3") (pin "2") (pinfunction "2_2") (pintype "passive"))
      (node (ref "U1") (pin "17") (pinfunction "PORTA_3_17") (pintype "bidirectional"))
    )
    (net (code "9") (name "I2C_SCL") (class "Default")
      (node (ref "R5") (pin "2") (pinfunction "2_2") (pintype "passive"))
      (node (ref "R8") (pin "1") (pinfunction "1_1") (pintype "passive"))
      (node (ref "U2") (pin "P2") (pinfunction "SCL_P2") (pintype "bidirectional"))
      (node (ref "U4") (pin "P8") (pinfunction "SCL_P8") (pintype "input"))
    )
    (net (code "10") (name "I2C_SDA") (class "Default")
      (node (ref "R6") (pin "2") (pinfunction "2_2") (pintype "passive"))
      (node (ref "R7") (pin "1") (pinfunction "1_1") (pintype "passive"))
      (node (ref "U2") (pin "P3") (pinfunction "SDA_P3") (pintype "bidirectional"))
      (node (ref "U4") (pin "P7") (pinfunction "SDA_P7") (pintype "bidirectional"))
    )
    (net (code "11") (name "LSM303_DRDY") (class "Default")
      (node (ref "U1") (pin "8") (pinfunction "PORTC_0_8") (pintype "bidirectional"))
      (node (ref "U2") (pin "P9") (pinfunction "DRDY_P9") (pintype "bidirectional"))
    )
    (net (code "12") (name "LSM303_INT1") (class "Default")
      (node (ref "U1") (pin "9") (pinfunction "PORTC_1_9") (pintype "bidirectional"))
      (node (ref "U2") (pin "P5") (pinfunction "INT1_P5") (pintype "bidirectional"))
    )
    (net (code "13") (name "LSM303_INT2") (class "Default")
      (node (ref "U1") (pin "10") (pinfunction "PORTC_2_10") (pintype "bidirectional"))
      (node (ref "U2") (pin "P4") (pinfunction "INT2_P4") (pintype "bidirectional"))
    )
    (net (code "14") (name "LSM330_DEN_GYRO") (class "Default")
      (node (ref "U1") (pin "11") (pinfunction "PORTC_3_11") (pintype "bidirectional"))
      (node (ref "U3") (pin "P16") (pinfunction "DEN_G_P16") (pintype "input"))
    )
    (net (code "15") (name "LSM330_DRDY_GYRO") (class "Default")
      (node (ref "U1") (pin "24") (pinfunction "PORTC_4_24") (pintype "bidirectional"))
      (node (ref "U3") (pin "P17") (pinfunction "DRDY_G_P17") (pintype "output"))
    )
    (net (code "16") (name "LSM330_INT1_ACCL") (class "Default")
      (node (ref "U1") (pin "37") (pinfunction "PORTC_6_37") (pintype "bidirectional"))
      (node (ref "U3") (pin "P20") (pinfunction "INT1_A_P20") (pintype "output"))
    )
    (net (code "17") (name "LSM330_INT1_GYRO") (class "Default")
      (node (ref "U1") (pin "25") (pinfunction "PORTC_5_25") (pintype "bidirectional"))
      (node (ref "U3") (pin "P18") (pinfunction "INT1_G_P18") (pintype "output"))
    )
    (net (code "18") (name "LSM330_INT2_ACCL") (class "Default")
      (node (ref "U1") (pin "38") (pinfunction "PORTC_7_38") (pintype "bidirectional"))
      (node (ref "U3") (pin "P19") (pinfunction "INT2_A_P19") (pintype "output"))
    )
    (net (code "19") (name "MPL311_P_INT1") (class "Default")
      (node (ref "U1") (pin "39") (pinfunction "PORTC_8_39") (pintype "bidirectional"))
      (node (ref "U4") (pin "P6") (pinfunction "INT1_P6") (pintype "output"))
    )
    (net (code "20") (name "MPL311_P_INT2") (class "Default")
      (node (ref "U1") (pin "40") (pinfunction "PORTC_9_40") (pintype "bidirectional"))
      (node (ref "U4") (pin "P5") (pinfunction "INT2_P5") (pintype "output"))
    )
    (net (code "21") (name "Net-(U1A-VCAP_1)") (class "Default")
      (node (ref "C2") (pin "1") (pinfunction "1_1") (pintype "passive"))
      (node (ref "U1") (pin "31") (pinfunction "VCAP_1_31") (pintype "bidirectional"))
    )
    (net (code "22") (name "Net-(U1A-VCAP_2)") (class "Default")
      (node (ref "C1") (pin "1") (pinfunction "1_1") (pintype "passive"))
      (node (ref "U1") (pin "47") (pinfunction "VCAP_2_47") (pintype "bidirectional"))
    )
    (net (code "23") (name "Net-(U1E-PORTH_0)") (class "Default")
      (node (ref "C8") (pin "1") (pinfunction "1_1") (pintype "passive"))
      (node (ref "U1") (pin "5") (pinfunction "PORTH_0_5") (pintype "bidirectional"))
      (node (ref "XTAL1") (pin "P$1") (pinfunction "Q1_P$1") (pintype "bidirectional"))
    )
    (net (code "24") (name "Net-(U1E-PORTH_1)") (class "Default")
      (node (ref "C7") (pin "1") (pinfunction "1_1") (pintype "passive"))
      (node (ref "U1") (pin "6") (pinfunction "PORTH_1_6") (pintype "bidirectional"))
      (node (ref "XTAL1") (pin "P$3") (pinfunction "Q2_P$3") (pintype "bidirectional"))
    )
    (net (code "25") (name "Net-(U2-C1)") (class "Default")
      (node (ref "C10") (pin "1") (pinfunction "1_1") (pintype "passive"))
      (node (ref "U2") (pin "P6") (pinfunction "C1_P6") (pintype "bidirectional"))
    )
    (net (code "26") (name "Net-(U2-SETC)") (class "Default")
      (node (ref "C12") (pin "2") (pinfunction "2_2") (pintype "passive"))
      (node (ref "U2") (pin "P13") (pinfunction "SETC_P13") (pintype "bidirectional"))
    )
    (net (code "27") (name "Net-(U2-SETP)") (class "Default")
      (node (ref "C12") (pin "1") (pinfunction "1_1") (pintype "passive"))
      (node (ref "U2") (pin "P12") (pinfunction "SETP_P12") (pintype "bidirectional"))
    )
    (net (code "28") (name "Net-(U3-CAP)") (class "Default")
      (node (ref "C13") (pin "1") (pinfunction "1_1") (pintype "passive"))
      (node (ref "U3") (pin "P15") (pinfunction "CAP_P15") (pintype "power_in"))
    )
    (net (code "29") (name "Net-(U4-CAP)") (class "Default")
      (node (ref "C16") (pin "1") (pinfunction "1_1") (pintype "passive"))
      (node (ref "U4") (pin "P2") (pinfunction "CAP_P2") (pintype "power_in"))
    )
    (net (code "30") (name "Net-(U5-RXD)") (class "Default")
      (node (ref "R4") (pin "1") (pinfunction "1_1") (pintype "passive"))
      (node (ref "U5") (pin "P10") (pinfunction "RXD_P10") (pintype "bidirectional"))
    )
    (net (code "31") (name "Net-(U5-TXD)") (class "Default")
      (node (ref "R3") (pin "1") (pinfunction "1_1") (pintype "passive"))
      (node (ref "U5") (pin "P9") (pinfunction "TXD_P9") (pintype "bidirectional"))
    )
    (net (code "32") (name "Net-(U5-VBACKUP)") (class "Default")
      (node (ref "C18") (pin "1") (pinfunction "1_1") (pintype "passive"))
      (node (ref "U5") (pin "P4") (pinfunction "VBACKUP_P4") (pintype "bidirectional"))
    )
    (net (code "33") (name "PB8") (class "Default")
      (node (ref "R5") (pin "1") (pinfunction "1_1") (pintype "passive"))
      (node (ref "U1") (pin "61") (pinfunction "PORTB_8_61") (pintype "bidirectional"))
    )
    (net (code "34") (name "PB9") (class "Default")
      (node (ref "R6") (pin "1") (pinfunction "1_1") (pintype "passive"))
      (node (ref "U1") (pin "62") (pinfunction "PORTB_9_62") (pintype "bidirectional"))
    )
    (net (code "35") (name "SPIEXT_CLK") (class "Default")
      (node (ref "P4") (pin "P$1") (pinfunction "CLK_P$1") (pintype "bidirectional"))
      (node (ref "U1") (pin "34") (pinfunction "PORTB_13_34") (pintype "bidirectional"))
    )
    (net (code "36") (name "SPIEXT_MISO") (class "Default")
      (node (ref "P4") (pin "P$3") (pinfunction "MISO_P$3") (pintype "bidirectional"))
      (node (ref "U1") (pin "35") (pinfunction "PORTB_14_35") (pintype "bidirectional"))
    )
    (net (code "37") (name "SPIEXT_MOSI") (class "Default")
      (node (ref "P4") (pin "P$2") (pinfunction "MOSI_P$2") (pintype "bidirectional"))
      (node (ref "U1") (pin "36") (pinfunction "PORTB_15_36") (pintype "bidirectional"))
    )
    (net (code "38") (name "SPIEXT_NSS") (class "Default")
      (node (ref "P4") (pin "P$4") (pinfunction "NSS_P$4") (pintype "bidirectional"))
      (node (ref "U1") (pin "33") (pinfunction "PORTB_12_33") (pintype "bidirectional"))
    )
    (net (code "39") (name "SPI_CLK") (class "Default")
      (node (ref "U1") (pin "21") (pinfunction "PORTA_5_21") (pintype "bidirectional"))
      (node (ref "U3") (pin "P24") (pinfunction "SCL_P24") (pintype "input"))
    )
    (net (code "40") (name "SPI_CS_ACCL") (class "Default")
      (node (ref "U1") (pin "14") (pinfunction "PORTA_0_14") (pintype "bidirectional"))
      (node (ref "U3") (pin "P23") (pinfunction "~{CS_A}_P23") (pintype "input"))
    )
    (net (code "41") (name "SPI_CS_GYRO") (class "Default")
      (node (ref "U1") (pin "15") (pinfunction "PORTA_1_15") (pintype "bidirectional"))
      (node (ref "U3") (pin "P22") (pinfunction "~{CS_G}_P22") (pintype "input"))
    )
    (net (code "42") (name "SPI_MISO") (class "Default")
      (node (ref "U1") (pin "22") (pinfunction "PORTA_6_22") (pintype "bidirectional"))
      (node (ref "U3") (pin "P26") (pinfunction "SDO_G_P26") (pintype "output"))
      (node (ref "U3") (pin "P27") (pinfunction "SDO_A_P27") (pintype "output"))
    )
    (net (code "43") (name "SPI_MOSI") (class "Default")
      (node (ref "U1") (pin "23") (pinfunction "PORTA_7_23") (pintype "bidirectional"))
      (node (ref "U3") (pin "P28") (pinfunction "SDA_P28") (pintype "input"))
    )
    (net (code "44") (name "SWCLK") (class "Default")
      (node (ref "P2") (pin "P$2") (pinfunction "SWCLK_P$2") (pintype "bidirectional"))
      (node (ref "U1") (pin "49") (pinfunction "PORTA_14_49") (pintype "bidirectional"))
    )
    (net (code "45") (name "SWDIO") (class "Default")
      (node (ref "P2") (pin "P$4") (pinfunction "SWDIO_P$4") (pintype "bidirectional"))
      (node (ref "U1") (pin "46") (pinfunction "PORTA_13_46") (pintype "bidirectional"))
    )
    (net (code "46") (name "VDD") (class "Default")
      (node (ref "BOOT") (pin "P1") (pinfunction "P$1_P1") (pintype "bidirectional"))
      (node (ref "BOOT") (pin "P2") (pinfunction "P$1_P2") (pintype "bidirectional"))
      (node (ref "C11") (pin "1") (pinfunction "1_1") (pintype "passive"))
      (node (ref "C14") (pin "1") (pinfunction "1_1") (pintype "passive"))
      (node (ref "C15") (pin "1") (pinfunction "1_1") (pintype "passive"))
      (node (ref "C17") (pin "1") (pinfunction "1_1") (pintype "passive"))
      (node (ref "C22") (pin "1") (pinfunction "1_1") (pintype "passive"))
      (node (ref "C3") (pin "1") (pinfunction "1_1") (pintype "passive"))
      (node (ref "C4") (pin "1") (pinfunction "1_1") (pintype "passive"))
      (node (ref "C5") (pin "1") (pinfunction "1_1") (pintype "passive"))
      (node (ref "C6") (pin "1") (pinfunction "1_1") (pintype "passive"))
      (node (ref "L1") (pin "1") (pinfunction "1_1") (pintype "passive"))
      (node (ref "P2") (pin "P$1") (pinfunction "VDD_T_P$1") (pintype "bidirectional"))
      (node (ref "P3") (pin "P$3") (pinfunction "VDD_3P3V_P$3") (pintype "bidirectional"))
      (node (ref "R1") (pin "2") (pinfunction "2_2") (pintype "passive"))
      (node (ref "R7") (pin "2") (pinfunction "2_2") (pintype "passive"))
      (node (ref "R8") (pin "2") (pinfunction "2_2") (pintype "passive"))
      (node (ref "U1") (pin "1") (pinfunction "VBAT_1") (pintype "bidirectional"))
      (node (ref "U1") (pin "13") (pinfunction "VDDA_13") (pintype "bidirectional"))
      (node (ref "U1") (pin "19") (pinfunction "VDD_19") (pintype "bidirectional"))
      (node (ref "U1") (pin "32") (pinfunction "VDD_32") (pintype "bidirectional"))
      (node (ref "U1") (pin "48") (pinfunction "VDD_48") (pintype "bidirectional"))
      (node (ref "U1") (pin "64") (pinfunction "VDD_64") (pintype "bidirectional"))
      (node (ref "U2") (pin "P1") (pinfunction "VDD_IO_P1") (pintype "bidirectional"))
      (node (ref "U2") (pin "P14") (pinfunction "VDD_P14") (pintype "bidirectional"))
      (node (ref "U3") (pin "P10") (pinfunction "VDD_P10") (pintype "power_in"))
      (node (ref "U3") (pin "P11") (pinfunction "VDD_P11") (pintype "power_in"))
      (node (ref "U3") (pin "P12") (pinfunction "VDD_P12") (pintype "power_in"))
      (node (ref "U3") (pin "P13") (pinfunction "VDD_P13") (pintype "power_in"))
      (node (ref "U3") (pin "P14") (pinfunction "VDD_P14") (pintype "power_in"))
      (node (ref "U3") (pin "P21") (pinfunction "VDD_IO_P21") (pintype "power_in"))
      (node (ref "U3") (pin "P25") (pinfunction "VDD_IO_P25") (pintype "power_in"))
      (node (ref "U3") (pin "P7") (pinfunction "VDD_P7") (pintype "power_in"))
      (node (ref "U3") (pin "P8") (pinfunction "VDD_P8") (pintype "power_in"))
      (node (ref "U3") (pin "P9") (pinfunction "VDD_P9") (pintype "power_in"))
      (node (ref "U4") (pin "P1") (pinfunction "VDD_P1") (pintype "power_in"))
      (node (ref "U4") (pin "P4") (pinfunction "VDD_IO_P4") (pintype "power_in"))
      (node (ref "U6") (pin "3") (pinfunction "OUT_3") (pintype "bidirectional"))
    )
    (net (code "47") (name "VDD_5") (class "Default")
      (node (ref "C21") (pin "1") (pinfunction "1_1") (pintype "passive"))
      (node (ref "P1") (pin "P1") (pinfunction "1_P1") (pintype "passive"))
      (node (ref "P3") (pin "P$2") (pinfunction "VDD_5P0V_P$2") (pintype "bidirectional"))
      (node (ref "U1") (pin "42") (pinfunction "PORTA_9_42") (pintype "bidirectional"))
      (node (ref "U6") (pin "1") (pinfunction "IN_1") (pintype "bidirectional"))
    )
    (net (code "48") (name "VDD_GPS") (class "Default")
      (node (ref "C19") (pin "1") (pinfunction "1_1") (pintype "passive"))
      (node (ref "C20") (pin "1") (pinfunction "1_1") (pintype "passive"))
      (node (ref "L1") (pin "2") (pinfunction "2_2") (pintype "passive"))
      (node (ref "U5") (pin "P1") (pinfunction "VDD_P1") (pintype "bidirectional"))
    )
    (net (code "49") (name "unconnected-(P1-4-PadP4)") (class "Default")
      (node (ref "P1") (pin "P4") (pinfunction "4_P4") (pintype "passive"))
    )
    (net (code "50") (name "unconnected-(U1B-PORTA_4-Pad20)") (class "Default")
      (node (ref "U1") (pin "20") (pinfunction "PORTA_4_20") (pintype "bidirectional"))
    )
    (net (code "51") (name "unconnected-(U1B-PORTA_8-Pad41)") (class "Default")
      (node (ref "U1") (pin "41") (pinfunction "PORTA_8_41") (pintype "bidirectional"))
    )
    (net (code "52") (name "unconnected-(U1B-PORTA_10-Pad43)") (class "Default")
      (node (ref "U1") (pin "43") (pinfunction "PORTA_10_43") (pintype "bidirectional"))
    )
    (net (code "53") (name "unconnected-(U1B-PORTA_15-Pad50)") (class "Default")
      (node (ref "U1") (pin "50") (pinfunction "PORTA_15_50") (pintype "bidirectional"))
    )
    (net (code "54") (name "unconnected-(U1C-PORTB_0-Pad26)") (class "Default")
      (node (ref "U1") (pin "26") (pinfunction "PORTB_0_26") (pintype "bidirectional"))
    )
    (net (code "55") (name "unconnected-(U1C-PORTB_1-Pad27)") (class "Default")
      (node (ref "U1") (pin "27") (pinfunction "PORTB_1_27") (pintype "bidirectional"))
    )
    (net (code "56") (name "unconnected-(U1C-PORTB_3-Pad55)") (class "Default")
      (node (ref "U1") (pin "55") (pinfunction "PORTB_3_55") (pintype "bidirectional"))
    )
    (net (code "57") (name "unconnected-(U1C-PORTB_4-Pad56)") (class "Default")
      (node (ref "U1") (pin "56") (pinfunction "PORTB_4_56") (pintype "bidirectional"))
    )
    (net (code "58") (name "unconnected-(U1C-PORTB_5-Pad57)") (class "Default")
      (node (ref "U1") (pin "57") (pinfunction "PORTB_5_57") (pintype "bidirectional"))
    )
    (net (code "59") (name "unconnected-(U1C-PORTB_6-Pad58)") (class "Default")
      (node (ref "U1") (pin "58") (pinfunction "PORTB_6_58") (pintype "bidirectional"))
    )
    (net (code "60") (name "unconnected-(U1C-PORTB_7-Pad59)") (class "Default")
      (node (ref "U1") (pin "59") (pinfunction "PORTB_7_59") (pintype "bidirectional"))
    )
    (net (code "61") (name "unconnected-(U1C-PORTB_10-Pad29)") (class "Default")
      (node (ref "U1") (pin "29") (pinfunction "PORTB_10_29") (pintype "bidirectional"))
    )
    (net (code "62") (name "unconnected-(U1C-PORTB_11-Pad30)") (class "Default")
      (node (ref "U1") (pin "30") (pinfunction "PORTB_11_30") (pintype "bidirectional"))
    )
    (net (code "63") (name "unconnected-(U1D-PORTC_12-Pad53)") (class "Default")
      (node (ref "U1") (pin "53") (pinfunction "PORTC_12_53") (pintype "bidirectional"))
    )
    (net (code "64") (name "unconnected-(U1D-PORTC_13-Pad2)") (class "Default")
      (node (ref "U1") (pin "2") (pinfunction "PORTC_13_2") (pintype "bidirectional"))
    )
    (net (code "65") (name "unconnected-(U1D-PORTC_14-Pad3)") (class "Default")
      (node (ref "U1") (pin "3") (pinfunction "PORTC_14_3") (pintype "bidirectional"))
    )
    (net (code "66") (name "unconnected-(U1D-PORTC_15-Pad4)") (class "Default")
      (node (ref "U1") (pin "4") (pinfunction "PORTC_15_4") (pintype "bidirectional"))
    )
    (net (code "67") (name "unconnected-(U1E-PORTD_2-Pad54)") (class "Default")
      (node (ref "U1") (pin "54") (pinfunction "PORTD_2_54") (pintype "bidirectional"))
    )
    (net (code "68") (name "unconnected-(U5-DMINUS-PadP7)") (class "Default")
      (node (ref "U5") (pin "P7") (pinfunction "DMINUS_P7") (pintype "bidirectional"))
    )
    (net (code "69") (name "unconnected-(U5-DPLUS-PadP6)") (class "Default")
      (node (ref "U5") (pin "P6") (pinfunction "DPLUS_P6") (pintype "bidirectional"))
    )
    (net (code "70") (name "~{RST}") (class "Default")
      (node (ref "C9") (pin "1") (pinfunction "1_1") (pintype "passive"))
      (node (ref "P2") (pin "P$5") (pinfunction "~{RST}_P$5") (pintype "bidirectional"))
      (node (ref "R1") (pin "1") (pinfunction "1_1") (pintype "passive"))
      (node (ref "RST") (pin "P3") (pinfunction "P$2_P3") (pintype "bidirectional"))
      (node (ref "RST") (pin "P4") (pinfunction "P$2_P4") (pintype "bidirectional"))
      (node (ref "U1") (pin "7") (pinfunction "~{RST}_7") (pintype "bidirectional"))
    )
  )
)
